# pcb_telemetria.net
KiCad netlist of a schematic drawn in EAGLE
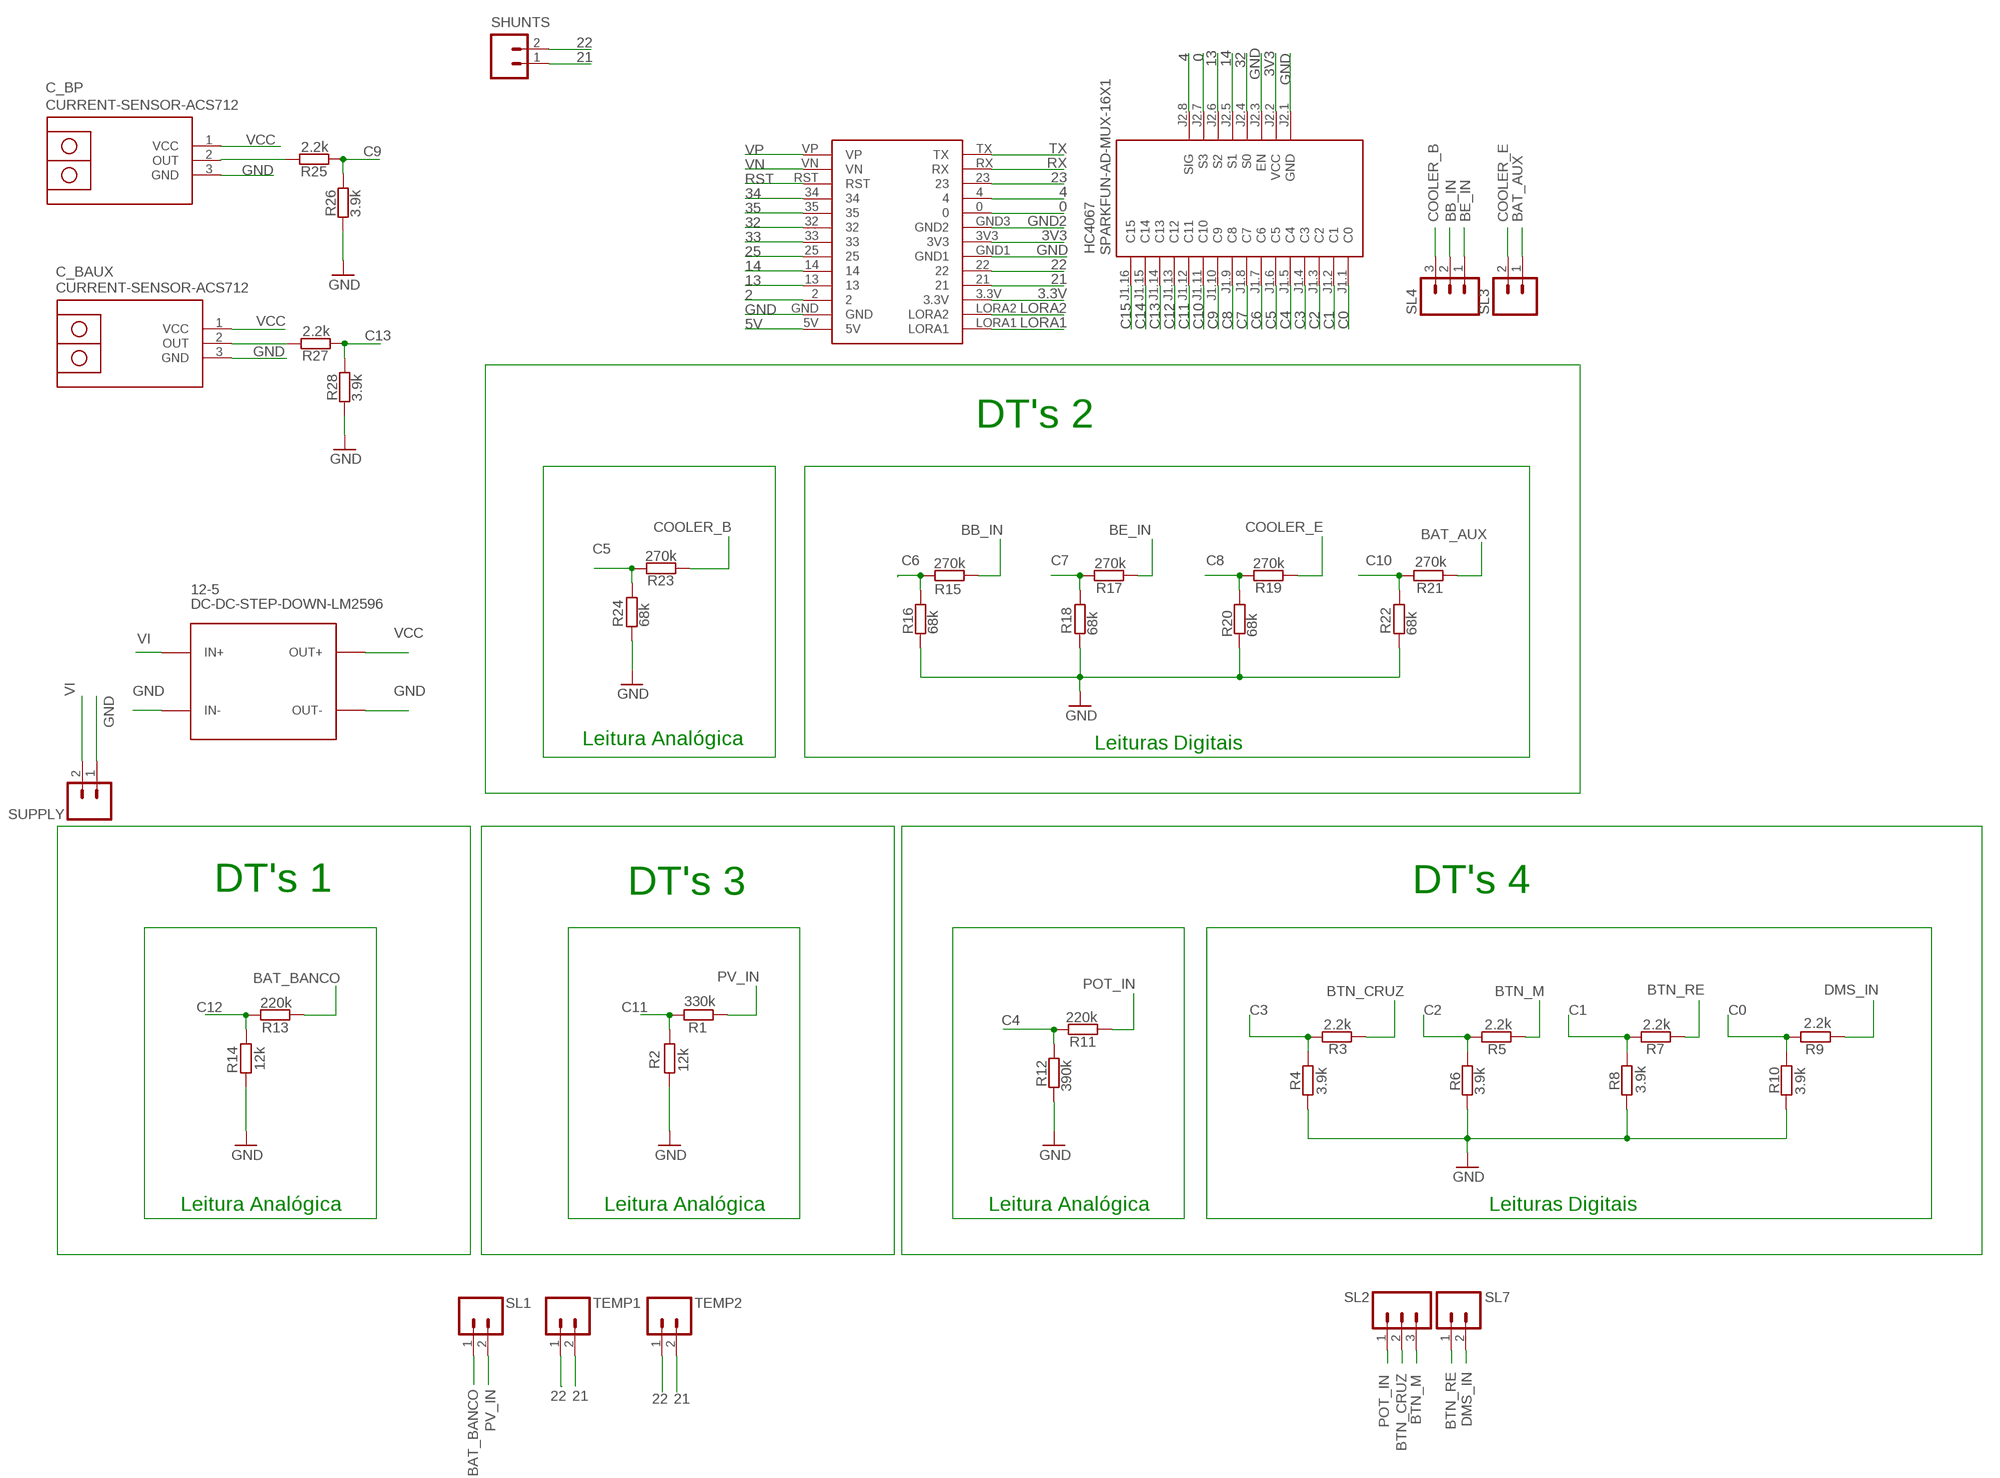
[diagram p0: schematic, sheet 1]

(export (version "E")
  (design (tool "Eeschema 10.0.6"))
  (components
    (comp (ref "12-5")
      (value "DC-DC-STEP-DOWN-LM2596")
      (footprint "eagle-import:DC-DC-STEP-DOWN-LM2596")
      (libsource (lib "eagle-import") (part "DC-DC-STEP-DOWN-LM2596"))
    )
    (comp (ref "C_BAUX")
      (value "CURRENT-SENSOR-ACS712")
      (footprint "eagle-import:CURRENT-SENSOR-ACS712")
      (libsource (lib "eagle-import") (part "CURRENT-SENSOR-ACS712"))
    )
    (comp (ref "C_BP")
      (value "CURRENT-SENSOR-ACS712")
      (footprint "eagle-import:CURRENT-SENSOR-ACS712")
      (libsource (lib "eagle-import") (part "CURRENT-SENSOR-ACS712"))
    )
    (comp (ref "HC4067")
      (value "SPARKFUN-AD-MUX-16X1")
      (footprint "eagle-import:SPARKFUN-AD-MUX-16X1")
      (libsource (lib "eagle-import") (part "SPARKFUN-AD-MUX-16X1"))
    )
    (comp (ref "R1")
      (value "330k")
      (footprint "eagle-import:0204_7")
      (libsource (lib "eagle-import") (part "R-EU_0204/7"))
    )
    (comp (ref "R2")
      (value "12k")
      (footprint "eagle-import:0204_7")
      (libsource (lib "eagle-import") (part "R-EU_0204/7"))
    )
    (comp (ref "R3")
      (value "2.2k")
      (footprint "eagle-import:0204_7")
      (libsource (lib "eagle-import") (part "R-EU_0204/7"))
    )
    (comp (ref "R4")
      (value "3.9k")
      (footprint "eagle-import:0204_7")
      (libsource (lib "eagle-import") (part "R-EU_0204/7"))
    )
    (comp (ref "R5")
      (value "2.2k")
      (footprint "eagle-import:0204_7")
      (libsource (lib "eagle-import") (part "R-EU_0204/7"))
    )
    (comp (ref "R6")
      (value "3.9k")
      (footprint "eagle-import:0204_7")
      (libsource (lib "eagle-import") (part "R-EU_0204/7"))
    )
    (comp (ref "R7")
      (value "2.2k")
      (footprint "eagle-import:0204_7")
      (libsource (lib "eagle-import") (part "R-EU_0204/7"))
    )
    (comp (ref "R8")
      (value "3.9k")
      (footprint "eagle-import:0204_7")
      (libsource (lib "eagle-import") (part "R-EU_0204/7"))
    )
    (comp (ref "R9")
      (value "2.2k")
      (footprint "eagle-import:0204_7")
      (libsource (lib "eagle-import") (part "R-EU_0204/7"))
    )
    (comp (ref "R10")
      (value "3.9k")
      (footprint "eagle-import:0204_7")
      (libsource (lib "eagle-import") (part "R-EU_0204/7"))
    )
    (comp (ref "R11")
      (value "220k")
      (footprint "eagle-import:0204_7")
      (libsource (lib "eagle-import") (part "R-EU_0204/7"))
    )
    (comp (ref "R12")
      (value "390k")
      (footprint "eagle-import:0204_7")
      (libsource (lib "eagle-import") (part "R-EU_0204/7"))
    )
    (comp (ref "R13")
      (value "220k")
      (footprint "eagle-import:0204_7")
      (libsource (lib "eagle-import") (part "R-EU_0204/7"))
    )
    (comp (ref "R14")
      (value "12k")
      (footprint "eagle-import:0204_7")
      (libsource (lib "eagle-import") (part "R-EU_0204/7"))
    )
    (comp (ref "R15")
      (value "270k")
      (footprint "eagle-import:0204_7")
      (libsource (lib "eagle-import") (part "R-EU_0204/7"))
    )
    (comp (ref "R16")
      (value "68k")
      (footprint "eagle-import:0204_7")
      (libsource (lib "eagle-import") (part "R-EU_0204/7"))
    )
    (comp (ref "R17")
      (value "270k")
      (footprint "eagle-import:0204_7")
      (libsource (lib "eagle-import") (part "R-EU_0204/7"))
    )
    (comp (ref "R18")
      (value "68k")
      (footprint "eagle-import:0204_7")
      (libsource (lib "eagle-import") (part "R-EU_0204/7"))
    )
    (comp (ref "R19")
      (value "270k")
      (footprint "eagle-import:0204_7")
      (libsource (lib "eagle-import") (part "R-EU_0204/7"))
    )
    (comp (ref "R20")
      (value "68k")
      (footprint "eagle-import:0204_7")
      (libsource (lib "eagle-import") (part "R-EU_0204/7"))
    )
    (comp (ref "R21")
      (value "270k")
      (footprint "eagle-import:0204_7")
      (libsource (lib "eagle-import") (part "R-EU_0204/7"))
    )
    (comp (ref "R22")
      (value "68k")
      (footprint "eagle-import:0204_7")
      (libsource (lib "eagle-import") (part "R-EU_0204/7"))
    )
    (comp (ref "R23")
      (value "270k")
      (footprint "eagle-import:0204_7")
      (libsource (lib "eagle-import") (part "R-EU_0204/7"))
    )
    (comp (ref "R24")
      (value "68k")
      (footprint "eagle-import:0204_7")
      (libsource (lib "eagle-import") (part "R-EU_0204/7"))
    )
    (comp (ref "R25")
      (value "2.2k")
      (footprint "eagle-import:0204_7")
      (libsource (lib "eagle-import") (part "R-EU_0204/7"))
    )
    (comp (ref "R26")
      (value "3.9k")
      (footprint "eagle-import:0204_7")
      (libsource (lib "eagle-import") (part "R-EU_0204/7"))
    )
    (comp (ref "R27")
      (value "2.2k")
      (footprint "eagle-import:0204_7")
      (libsource (lib "eagle-import") (part "R-EU_0204/7"))
    )
    (comp (ref "R28")
      (value "3.9k")
      (footprint "eagle-import:0204_7")
      (libsource (lib "eagle-import") (part "R-EU_0204/7"))
    )
    (comp (ref "SHUNTS")
      (value "M02")
      (footprint "eagle-import:02P")
      (libsource (lib "eagle-import") (part "M02"))
    )
    (comp (ref "SL1")
      (value "M02")
      (footprint "eagle-import:02P")
      (libsource (lib "eagle-import") (part "M02"))
    )
    (comp (ref "SL2")
      (value "M03")
      (footprint "eagle-import:03P")
      (libsource (lib "eagle-import") (part "M03"))
    )
    (comp (ref "SL3")
      (value "M02")
      (footprint "eagle-import:02P")
      (libsource (lib "eagle-import") (part "M02"))
    )
    (comp (ref "SL4")
      (value "M03")
      (footprint "eagle-import:03P")
      (libsource (lib "eagle-import") (part "M03"))
    )
    (comp (ref "SL7")
      (value "M02")
      (footprint "eagle-import:02P")
      (libsource (lib "eagle-import") (part "M02"))
    )
    (comp (ref "SUPPLY")
      (value "M02")
      (footprint "eagle-import:02P")
      (libsource (lib "eagle-import") (part "M02"))
    )
    (comp (ref "TEMP1")
      (value "M02")
      (footprint "eagle-import:02P")
      (libsource (lib "eagle-import") (part "M02"))
    )
    (comp (ref "TEMP2")
      (value "M02")
      (footprint "eagle-import:02P")
      (libsource (lib "eagle-import") (part "M02"))
    )
    (comp (ref "U$1")
      (value "TTGOBEAM")
      (footprint "eagle-import:TTGOBEAM")
      (libsource (lib "eagle-import") (part "TTGOBEAM"))
    )
  )
  (nets
    (net (code "1") (name "/0") (class "Default")
      (node (ref "HC4067") (pin "J2.7") (pinfunction "S3_J2.7") (pintype "bidirectional"))
      (node (ref "U$1") (pin "0") (pinfunction "0_0") (pintype "bidirectional"))
    )
    (net (code "2") (name "/2") (class "Default")
      (node (ref "U$1") (pin "2") (pinfunction "2_2") (pintype "bidirectional"))
    )
    (net (code "3") (name "/3.3V") (class "Default")
      (node (ref "U$1") (pin "3.3V") (pinfunction "3.3V_3.3V") (pintype "bidirectional"))
    )
    (net (code "4") (name "/3V3") (class "Default")
      (node (ref "HC4067") (pin "J2.2") (pinfunction "VCC_J2.2") (pintype "power_in"))
      (node (ref "U$1") (pin "3V3") (pinfunction "3V3_3V3") (pintype "bidirectional"))
    )
    (net (code "5") (name "/4") (class "Default")
      (node (ref "HC4067") (pin "J2.8") (pinfunction "SIG_J2.8") (pintype "bidirectional"))
      (node (ref "U$1") (pin "4") (pinfunction "4_4") (pintype "bidirectional"))
    )
    (net (code "6") (name "/5V") (class "Default")
      (node (ref "U$1") (pin "5V") (pinfunction "5V_5V") (pintype "bidirectional"))
    )
    (net (code "7") (name "/13") (class "Default")
      (node (ref "HC4067") (pin "J2.6") (pinfunction "S2_J2.6") (pintype "bidirectional"))
      (node (ref "U$1") (pin "13") (pinfunction "13_13") (pintype "bidirectional"))
    )
    (net (code "8") (name "/14") (class "Default")
      (node (ref "HC4067") (pin "J2.5") (pinfunction "S1_J2.5") (pintype "bidirectional"))
      (node (ref "U$1") (pin "14") (pinfunction "14_14") (pintype "bidirectional"))
    )
    (net (code "9") (name "/21") (class "Default")
      (node (ref "SHUNTS") (pin "1") (pinfunction "1_1") (pintype "passive"))
      (node (ref "TEMP1") (pin "2") (pinfunction "2_2") (pintype "passive"))
      (node (ref "TEMP2") (pin "2") (pinfunction "2_2") (pintype "passive"))
      (node (ref "U$1") (pin "21") (pinfunction "21_21") (pintype "bidirectional"))
    )
    (net (code "10") (name "/22") (class "Default")
      (node (ref "SHUNTS") (pin "2") (pinfunction "2_2") (pintype "passive"))
      (node (ref "TEMP1") (pin "1") (pinfunction "1_1") (pintype "passive"))
      (node (ref "TEMP2") (pin "1") (pinfunction "1_1") (pintype "passive"))
      (node (ref "U$1") (pin "22") (pinfunction "22_22") (pintype "bidirectional"))
    )
    (net (code "11") (name "/23") (class "Default")
      (node (ref "U$1") (pin "23") (pinfunction "23_23") (pintype "bidirectional"))
    )
    (net (code "12") (name "/25") (class "Default")
      (node (ref "U$1") (pin "25") (pinfunction "25_25") (pintype "bidirectional"))
    )
    (net (code "13") (name "/32") (class "Default")
      (node (ref "HC4067") (pin "J2.4") (pinfunction "S0_J2.4") (pintype "bidirectional"))
      (node (ref "U$1") (pin "32") (pinfunction "32_32") (pintype "bidirectional"))
    )
    (net (code "14") (name "/33") (class "Default")
      (node (ref "U$1") (pin "33") (pinfunction "33_33") (pintype "bidirectional"))
    )
    (net (code "15") (name "/34") (class "Default")
      (node (ref "U$1") (pin "34") (pinfunction "34_34") (pintype "bidirectional"))
    )
    (net (code "16") (name "/35") (class "Default")
      (node (ref "U$1") (pin "35") (pinfunction "35_35") (pintype "bidirectional"))
    )
    (net (code "17") (name "/BAT_AUX") (class "Default")
      (node (ref "R21") (pin "2") (pinfunction "2_2") (pintype "passive"))
      (node (ref "SL3") (pin "1") (pinfunction "1_1") (pintype "passive"))
    )
    (net (code "18") (name "/BAT_BANCO") (class "Default")
      (node (ref "R13") (pin "2") (pinfunction "2_2") (pintype "passive"))
      (node (ref "SL1") (pin "1") (pinfunction "1_1") (pintype "passive"))
    )
    (net (code "19") (name "/BB_IN") (class "Default")
      (node (ref "R15") (pin "1") (pinfunction "1_1") (pintype "passive"))
      (node (ref "SL4") (pin "2") (pinfunction "2_2") (pintype "passive"))
    )
    (net (code "20") (name "/BE_IN") (class "Default")
      (node (ref "R17") (pin "2") (pinfunction "2_2") (pintype "passive"))
      (node (ref "SL4") (pin "1") (pinfunction "1_1") (pintype "passive"))
    )
    (net (code "21") (name "/BTN_CRUZ") (class "Default")
      (node (ref "R3") (pin "1") (pinfunction "1_1") (pintype "passive"))
      (node (ref "SL2") (pin "2") (pinfunction "2_2") (pintype "passive"))
    )
    (net (code "22") (name "/BTN_M") (class "Default")
      (node (ref "R5") (pin "2") (pinfunction "2_2") (pintype "passive"))
      (node (ref "SL2") (pin "3") (pinfunction "3_3") (pintype "passive"))
    )
    (net (code "23") (name "/BTN_RE") (class "Default")
      (node (ref "R7") (pin "1") (pinfunction "1_1") (pintype "passive"))
      (node (ref "SL7") (pin "1") (pinfunction "1_1") (pintype "passive"))
    )
    (net (code "24") (name "/C0") (class "Default")
      (node (ref "HC4067") (pin "J1.1") (pinfunction "C0_J1.1") (pintype "bidirectional"))
      (node (ref "R10") (pin "2") (pinfunction "2_2") (pintype "passive"))
      (node (ref "R9") (pin "1") (pinfunction "1_1") (pintype "passive"))
    )
    (net (code "25") (name "/C1") (class "Default")
      (node (ref "HC4067") (pin "J1.2") (pinfunction "C1_J1.2") (pintype "bidirectional"))
      (node (ref "R7") (pin "2") (pinfunction "2_2") (pintype "passive"))
      (node (ref "R8") (pin "1") (pinfunction "1_1") (pintype "passive"))
    )
    (net (code "26") (name "/C2") (class "Default")
      (node (ref "HC4067") (pin "J1.3") (pinfunction "C2_J1.3") (pintype "bidirectional"))
      (node (ref "R5") (pin "1") (pinfunction "1_1") (pintype "passive"))
      (node (ref "R6") (pin "2") (pinfunction "2_2") (pintype "passive"))
    )
    (net (code "27") (name "/C3") (class "Default")
      (node (ref "HC4067") (pin "J1.4") (pinfunction "C3_J1.4") (pintype "bidirectional"))
      (node (ref "R3") (pin "2") (pinfunction "2_2") (pintype "passive"))
      (node (ref "R4") (pin "1") (pinfunction "1_1") (pintype "passive"))
    )
    (net (code "28") (name "/C4") (class "Default")
      (node (ref "HC4067") (pin "J1.5") (pinfunction "C4_J1.5") (pintype "bidirectional"))
      (node (ref "R11") (pin "2") (pinfunction "2_2") (pintype "passive"))
      (node (ref "R12") (pin "1") (pinfunction "1_1") (pintype "passive"))
    )
    (net (code "29") (name "/C5") (class "Default")
      (node (ref "HC4067") (pin "J1.6") (pinfunction "C5_J1.6") (pintype "bidirectional"))
      (node (ref "R23") (pin "2") (pinfunction "2_2") (pintype "passive"))
      (node (ref "R24") (pin "1") (pinfunction "1_1") (pintype "passive"))
    )
    (net (code "30") (name "/C6") (class "Default")
      (node (ref "HC4067") (pin "J1.7") (pinfunction "C6_J1.7") (pintype "bidirectional"))
      (node (ref "R15") (pin "2") (pinfunction "2_2") (pintype "passive"))
      (node (ref "R16") (pin "1") (pinfunction "1_1") (pintype "passive"))
    )
    (net (code "31") (name "/C7") (class "Default")
      (node (ref "HC4067") (pin "J1.8") (pinfunction "C7_J1.8") (pintype "bidirectional"))
      (node (ref "R17") (pin "1") (pinfunction "1_1") (pintype "passive"))
      (node (ref "R18") (pin "2") (pinfunction "2_2") (pintype "passive"))
    )
    (net (code "32") (name "/C8") (class "Default")
      (node (ref "HC4067") (pin "J1.9") (pinfunction "C8_J1.9") (pintype "bidirectional"))
      (node (ref "R19") (pin "2") (pinfunction "2_2") (pintype "passive"))
      (node (ref "R20") (pin "1") (pinfunction "1_1") (pintype "passive"))
    )
    (net (code "33") (name "/C9") (class "Default")
      (node (ref "HC4067") (pin "J1.10") (pinfunction "C9_J1.10") (pintype "bidirectional"))
      (node (ref "R25") (pin "1") (pinfunction "1_1") (pintype "passive"))
      (node (ref "R26") (pin "1") (pinfunction "1_1") (pintype "passive"))
    )
    (net (code "34") (name "/C10") (class "Default")
      (node (ref "HC4067") (pin "J1.11") (pinfunction "C10_J1.11") (pintype "bidirectional"))
      (node (ref "R21") (pin "1") (pinfunction "1_1") (pintype "passive"))
      (node (ref "R22") (pin "2") (pinfunction "2_2") (pintype "passive"))
    )
    (net (code "35") (name "/C11") (class "Default")
      (node (ref "HC4067") (pin "J1.12") (pinfunction "C11_J1.12") (pintype "bidirectional"))
      (node (ref "R1") (pin "1") (pinfunction "1_1") (pintype "passive"))
      (node (ref "R2") (pin "2") (pinfunction "2_2") (pintype "passive"))
    )
    (net (code "36") (name "/C12") (class "Default")
      (node (ref "HC4067") (pin "J1.13") (pinfunction "C12_J1.13") (pintype "bidirectional"))
      (node (ref "R13") (pin "1") (pinfunction "1_1") (pintype "passive"))
      (node (ref "R14") (pin "2") (pinfunction "2_2") (pintype "passive"))
    )
    (net (code "37") (name "/C13") (class "Default")
      (node (ref "HC4067") (pin "J1.14") (pinfunction "C13_J1.14") (pintype "bidirectional"))
      (node (ref "R27") (pin "1") (pinfunction "1_1") (pintype "passive"))
      (node (ref "R28") (pin "1") (pinfunction "1_1") (pintype "passive"))
    )
    (net (code "38") (name "/C14") (class "Default")
      (node (ref "HC4067") (pin "J1.15") (pinfunction "C14_J1.15") (pintype "bidirectional"))
    )
    (net (code "39") (name "/C15") (class "Default")
      (node (ref "HC4067") (pin "J1.16") (pinfunction "C15_J1.16") (pintype "bidirectional"))
    )
    (net (code "40") (name "/COOLER_B") (class "Default")
      (node (ref "R23") (pin "1") (pinfunction "1_1") (pintype "passive"))
      (node (ref "SL4") (pin "3") (pinfunction "3_3") (pintype "passive"))
    )
    (net (code "41") (name "/COOLER_E") (class "Default")
      (node (ref "R19") (pin "1") (pinfunction "1_1") (pintype "passive"))
      (node (ref "SL3") (pin "2") (pinfunction "2_2") (pintype "passive"))
    )
    (net (code "42") (name "/DMS_IN") (class "Default")
      (node (ref "R9") (pin "2") (pinfunction "2_2") (pintype "passive"))
      (node (ref "SL7") (pin "2") (pinfunction "2_2") (pintype "passive"))
    )
    (net (code "43") (name "/GND2") (class "Default")
      (node (ref "U$1") (pin "GND3") (pinfunction "GND2_GND3") (pintype "bidirectional"))
    )
    (net (code "44") (name "/LORA1") (class "Default")
      (node (ref "U$1") (pin "LORA1") (pinfunction "LORA1_LORA1") (pintype "bidirectional"))
    )
    (net (code "45") (name "/LORA2") (class "Default")
      (node (ref "U$1") (pin "LORA2") (pinfunction "LORA2_LORA2") (pintype "bidirectional"))
    )
    (net (code "46") (name "/POT_IN") (class "Default")
      (node (ref "R11") (pin "1") (pinfunction "1_1") (pintype "passive"))
      (node (ref "SL2") (pin "1") (pinfunction "1_1") (pintype "passive"))
    )
    (net (code "47") (name "/PV_IN") (class "Default")
      (node (ref "R1") (pin "2") (pinfunction "2_2") (pintype "passive"))
      (node (ref "SL1") (pin "2") (pinfunction "2_2") (pintype "passive"))
    )
    (net (code "48") (name "/RST") (class "Default")
      (node (ref "U$1") (pin "RST") (pinfunction "RST_RST") (pintype "bidirectional"))
    )
    (net (code "49") (name "/RX") (class "Default")
      (node (ref "U$1") (pin "RX") (pinfunction "RX_RX") (pintype "bidirectional"))
    )
    (net (code "50") (name "/TX") (class "Default")
      (node (ref "U$1") (pin "TX") (pinfunction "TX_TX") (pintype "bidirectional"))
    )
    (net (code "51") (name "/VCC") (class "Default")
      (node (ref "12-5") (pin "OUT+") (pinfunction "OUT+_OUT+") (pintype "bidirectional"))
      (node (ref "C_BAUX") (pin "1") (pinfunction "VCC_1") (pintype "power_in"))
      (node (ref "C_BP") (pin "1") (pinfunction "VCC_1") (pintype "power_in"))
    )
    (net (code "52") (name "/VI") (class "Default")
      (node (ref "12-5") (pin "IN+") (pinfunction "IN+_IN+") (pintype "bidirectional"))
      (node (ref "SUPPLY") (pin "2") (pinfunction "2_2") (pintype "passive"))
    )
    (net (code "53") (name "/VN") (class "Default")
      (node (ref "U$1") (pin "VN") (pinfunction "VN_VN") (pintype "bidirectional"))
    )
    (net (code "54") (name "/VP") (class "Default")
      (node (ref "U$1") (pin "VP") (pinfunction "VP_VP") (pintype "bidirectional"))
    )
    (net (code "55") (name "GND") (class "Default")
      (node (ref "12-5") (pin "IN-") (pinfunction "IN-_IN-") (pintype "bidirectional"))
      (node (ref "12-5") (pin "OUT-") (pinfunction "OUT-_OUT-") (pintype "bidirectional"))
      (node (ref "C_BAUX") (pin "3") (pinfunction "GND_3") (pintype "power_in"))
      (node (ref "C_BP") (pin "3") (pinfunction "GND_3") (pintype "power_in"))
      (node (ref "HC4067") (pin "J2.1") (pinfunction "GND_J2.1") (pintype "power_in"))
      (node (ref "HC4067") (pin "J2.3") (pinfunction "EN_J2.3") (pintype "input"))
      (node (ref "R10") (pin "1") (pinfunction "1_1") (pintype "passive"))
      (node (ref "R12") (pin "2") (pinfunction "2_2") (pintype "passive"))
      (node (ref "R14") (pin "1") (pinfunction "1_1") (pintype "passive"))
      (node (ref "R16") (pin "2") (pinfunction "2_2") (pintype "passive"))
      (node (ref "R18") (pin "1") (pinfunction "1_1") (pintype "passive"))
      (node (ref "R2") (pin "1") (pinfunction "1_1") (pintype "passive"))
      (node (ref "R20") (pin "2") (pinfunction "2_2") (pintype "passive"))
      (node (ref "R22") (pin "1") (pinfunction "1_1") (pintype "passive"))
      (node (ref "R24") (pin "2") (pinfunction "2_2") (pintype "passive"))
      (node (ref "R26") (pin "2") (pinfunction "2_2") (pintype "passive"))
      (node (ref "R28") (pin "2") (pinfunction "2_2") (pintype "passive"))
      (node (ref "R4") (pin "2") (pinfunction "2_2") (pintype "passive"))
      (node (ref "R6") (pin "1") (pinfunction "1_1") (pintype "passive"))
      (node (ref "R8") (pin "2") (pinfunction "2_2") (pintype "passive"))
      (node (ref "SUPPLY") (pin "1") (pinfunction "1_1") (pintype "passive"))
      (node (ref "U$1") (pin "GND") (pinfunction "GND_GND") (pintype "bidirectional"))
      (node (ref "U$1") (pin "GND1") (pinfunction "GND1_GND1") (pintype "bidirectional"))
    )
    (net (code "56") (name "Net-(C_BAUX-OUT)") (class "Default")
      (node (ref "C_BAUX") (pin "2") (pinfunction "OUT_2") (pintype "output"))
      (node (ref "R27") (pin "2") (pinfunction "2_2") (pintype "passive"))
    )
    (net (code "57") (name "Net-(C_BP-OUT)") (class "Default")
      (node (ref "C_BP") (pin "2") (pinfunction "OUT_2") (pintype "output"))
      (node (ref "R25") (pin "2") (pinfunction "2_2") (pintype "passive"))
    )
  )
)
